# Sheet1.net
KiCad netlist of a schematic drawn in Altium Designer
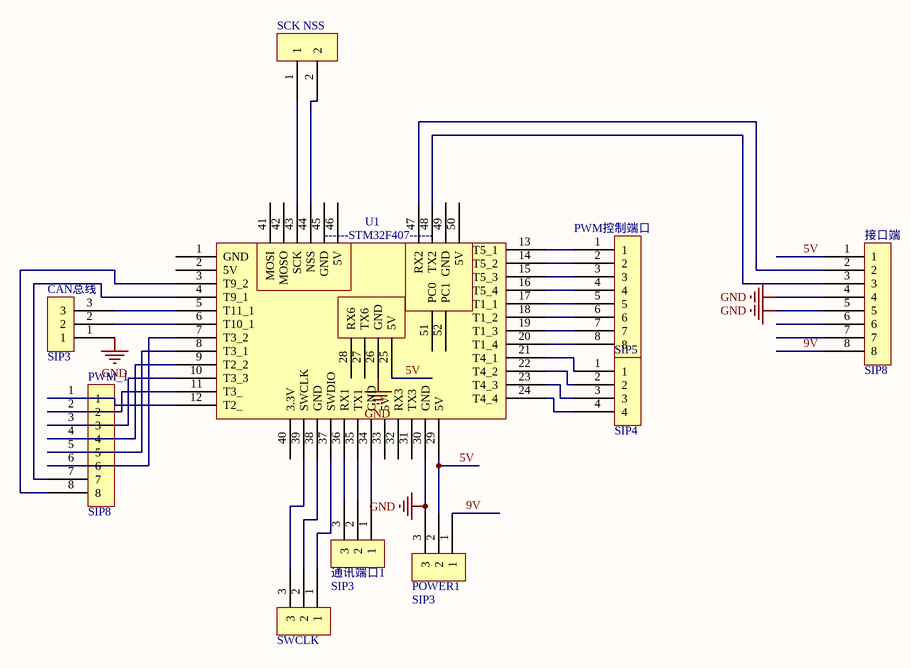
[diagram p0: Sheet1.SchDoc]

(export (version "E")
  (design (tool "Eeschema 10.0.6"))
  (components
    (comp (ref "CAN总线") (value "SIP3") (footprint "SIP3") (libsource (lib "") (part "SIP3_1")))
    (comp (ref "POWER1") (value "SIP3") (footprint "SIP3") (libsource (lib "qudong") (part "SIP3")))
    (comp (ref "PWM_1") (value "SIP8") (footprint "SIP8") (libsource (lib "qudong") (part "SIP8")))
    (comp (ref "PWM控制端口") (value "PWM控制端口") (footprint "SIP8") (libsource (lib "qudong") (part "SIP8")))
    (comp (ref "SCK NSS") (value "SIP2") (footprint "SIP2") (libsource (lib "qudong") (part "SIP2")))
    (comp (ref "SIP5") (value "SIP4") (footprint "SIP4") (libsource (lib "qudong") (part "SIP4")))
    (comp (ref "SWCLK") (value "SIP3") (footprint "SIP3") (libsource (lib "qudong") (part "SIP3")))
    (comp (ref "U1")
      (value "------STM32F407------")
      (footprint "-----STM32F407-----")
      (libsource (lib "qudong") (part "------STM32F407------"))
    )
    (comp (ref "接口端") (value "SIP8") (footprint "SIP8") (libsource (lib "qudong") (part "SIP8")))
    (comp (ref "通讯端口1") (value "SIP3") (footprint "SIP3") (libsource (lib "qudong") (part "SIP3")))
  )
  (nets
    (net (code "1") (name "/5V") (class "Default")
      (node (ref "POWER1") (pin "2") (pinfunction "2_2") (pintype "passive"))
      (node (ref "U1") (pin "25") (pinfunction "5V_25") (pintype "passive"))
      (node (ref "U1") (pin "29") (pinfunction "5V_29") (pintype "passive"))
      (node (ref "接口端") (pin "1") (pinfunction "1_1") (pintype "passive"))
    )
    (net (code "2") (name "/9V") (class "Default")
      (node (ref "POWER1") (pin "1") (pinfunction "1_1") (pintype "passive"))
      (node (ref "接口端") (pin "8") (pinfunction "8_8") (pintype "passive"))
    )
    (net (code "3") (name "GND") (class "Default")
      (node (ref "CAN总线") (pin "1") (pinfunction "1_1") (pintype "passive"))
      (node (ref "POWER1") (pin "3") (pinfunction "3_3") (pintype "passive"))
      (node (ref "U1") (pin "26") (pinfunction "GND_26") (pintype "passive"))
      (node (ref "U1") (pin "30") (pinfunction "GND_30") (pintype "passive"))
      (node (ref "接口端") (pin "4") (pinfunction "4_4") (pintype "passive"))
      (node (ref "接口端") (pin "5") (pinfunction "5_5") (pintype "passive"))
    )
    (net (code "4") (name "Net-(SWCLK-Pad2)") (class "Default")
      (node (ref "SWCLK") (pin "2") (pinfunction "2_2") (pintype "passive"))
      (node (ref "U1") (pin "38") (pinfunction "GND_38") (pintype "passive"))
    )
    (net (code "5") (name "Net-(U1-GND-Pad34)") (class "Default")
      (node (ref "U1") (pin "34") (pinfunction "GND_34") (pintype "passive"))
      (node (ref "通讯端口1") (pin "1") (pinfunction "1_1") (pintype "passive"))
    )
    (net (code "6") (name "Net-(U1-NSS)") (class "Default")
      (node (ref "SCK NSS") (pin "2") (pinfunction "2_2") (pintype "passive"))
      (node (ref "U1") (pin "44") (pinfunction "NSS_44") (pintype "passive"))
    )
    (net (code "7") (name "Net-(U1-RX1)") (class "Default")
      (node (ref "U1") (pin "36") (pinfunction "RX1_36") (pintype "passive"))
      (node (ref "通讯端口1") (pin "3") (pinfunction "3_3") (pintype "passive"))
    )
    (net (code "8") (name "Net-(U1-RX2)") (class "Default")
      (node (ref "U1") (pin "47") (pinfunction "RX2_47") (pintype "passive"))
      (node (ref "接口端") (pin "2") (pinfunction "2_2") (pintype "passive"))
    )
    (net (code "9") (name "Net-(U1-SCK)") (class "Default")
      (node (ref "SCK NSS") (pin "1") (pinfunction "1_1") (pintype "passive"))
      (node (ref "U1") (pin "43") (pinfunction "SCK_43") (pintype "passive"))
    )
    (net (code "10") (name "Net-(U1-SWCLK)") (class "Default")
      (node (ref "SWCLK") (pin "3") (pinfunction "3_3") (pintype "passive"))
      (node (ref "U1") (pin "39") (pinfunction "SWCLK_39") (pintype "passive"))
    )
    (net (code "11") (name "Net-(U1-SWDIO)") (class "Default")
      (node (ref "SWCLK") (pin "1") (pinfunction "1_1") (pintype "passive"))
      (node (ref "U1") (pin "37") (pinfunction "SWDIO_37") (pintype "passive"))
    )
    (net (code "12") (name "Net-(U1-T1_1)") (class "Default")
      (node (ref "PWM控制端口") (pin "5") (pinfunction "5_5") (pintype "passive"))
      (node (ref "U1") (pin "17") (pinfunction "T1_1_17") (pintype "passive"))
    )
    (net (code "13") (name "Net-(U1-T1_2)") (class "Default")
      (node (ref "PWM控制端口") (pin "6") (pinfunction "6_6") (pintype "passive"))
      (node (ref "U1") (pin "18") (pinfunction "T1_2_18") (pintype "passive"))
    )
    (net (code "14") (name "Net-(U1-T1_3)") (class "Default")
      (node (ref "PWM控制端口") (pin "7") (pinfunction "7_7") (pintype "passive"))
      (node (ref "U1") (pin "19") (pinfunction "T1_3_19") (pintype "passive"))
    )
    (net (code "15") (name "Net-(U1-T1_4)") (class "Default")
      (node (ref "PWM控制端口") (pin "8") (pinfunction "8_8") (pintype "passive"))
      (node (ref "U1") (pin "20") (pinfunction "T1_4_20") (pintype "passive"))
    )
    (net (code "16") (name "Net-(U1-T2_)") (class "Default")
      (node (ref "PWM_1") (pin "1") (pinfunction "1_1") (pintype "passive"))
      (node (ref "U1") (pin "12") (pinfunction "T2__12") (pintype "passive"))
    )
    (net (code "17") (name "Net-(U1-T2_2)") (class "Default")
      (node (ref "PWM_1") (pin "4") (pinfunction "4_4") (pintype "passive"))
      (node (ref "U1") (pin "9") (pinfunction "T2_2_9") (pintype "passive"))
    )
    (net (code "18") (name "Net-(U1-T3_)") (class "Default")
      (node (ref "PWM_1") (pin "2") (pinfunction "2_2") (pintype "passive"))
      (node (ref "U1") (pin "11") (pinfunction "T3__11") (pintype "passive"))
    )
    (net (code "19") (name "Net-(U1-T3_1)") (class "Default")
      (node (ref "PWM_1") (pin "5") (pinfunction "5_5") (pintype "passive"))
      (node (ref "U1") (pin "8") (pinfunction "T3_1_8") (pintype "passive"))
    )
    (net (code "20") (name "Net-(U1-T3_2)") (class "Default")
      (node (ref "PWM_1") (pin "6") (pinfunction "6_6") (pintype "passive"))
      (node (ref "U1") (pin "7") (pinfunction "T3_2_7") (pintype "passive"))
    )
    (net (code "21") (name "Net-(U1-T3_3)") (class "Default")
      (node (ref "PWM_1") (pin "3") (pinfunction "3_3") (pintype "passive"))
      (node (ref "U1") (pin "10") (pinfunction "T3_3_10") (pintype "passive"))
    )
    (net (code "22") (name "Net-(U1-T4_1)") (class "Default")
      (node (ref "SIP5") (pin "1") (pinfunction "1_1") (pintype "passive"))
      (node (ref "U1") (pin "21") (pinfunction "T4_1_21") (pintype "passive"))
    )
    (net (code "23") (name "Net-(U1-T4_2)") (class "Default")
      (node (ref "SIP5") (pin "2") (pinfunction "2_2") (pintype "passive"))
      (node (ref "U1") (pin "22") (pinfunction "T4_2_22") (pintype "passive"))
    )
    (net (code "24") (name "Net-(U1-T4_3)") (class "Default")
      (node (ref "SIP5") (pin "3") (pinfunction "3_3") (pintype "passive"))
      (node (ref "U1") (pin "23") (pinfunction "T4_3_23") (pintype "passive"))
    )
    (net (code "25") (name "Net-(U1-T4_4)") (class "Default")
      (node (ref "SIP5") (pin "4") (pinfunction "4_4") (pintype "passive"))
      (node (ref "U1") (pin "24") (pinfunction "T4_4_24") (pintype "passive"))
    )
    (net (code "26") (name "Net-(U1-T5_1)") (class "Default")
      (node (ref "PWM控制端口") (pin "1") (pinfunction "1_1") (pintype "passive"))
      (node (ref "U1") (pin "13") (pinfunction "T5_1_13") (pintype "passive"))
    )
    (net (code "27") (name "Net-(U1-T5_2)") (class "Default")
      (node (ref "PWM控制端口") (pin "2") (pinfunction "2_2") (pintype "passive"))
      (node (ref "U1") (pin "14") (pinfunction "T5_2_14") (pintype "passive"))
    )
    (net (code "28") (name "Net-(U1-T5_3)") (class "Default")
      (node (ref "PWM控制端口") (pin "3") (pinfunction "3_3") (pintype "passive"))
      (node (ref "U1") (pin "15") (pinfunction "T5_3_15") (pintype "passive"))
    )
    (net (code "29") (name "Net-(U1-T5_4)") (class "Default")
      (node (ref "PWM控制端口") (pin "4") (pinfunction "4_4") (pintype "passive"))
      (node (ref "U1") (pin "16") (pinfunction "T5_4_16") (pintype "passive"))
    )
    (net (code "30") (name "Net-(U1-T9_1)") (class "Default")
      (node (ref "PWM_1") (pin "7") (pinfunction "7_7") (pintype "passive"))
      (node (ref "U1") (pin "4") (pinfunction "T9_1_4") (pintype "passive"))
    )
    (net (code "31") (name "Net-(U1-T9_2)") (class "Default")
      (node (ref "PWM_1") (pin "8") (pinfunction "8_8") (pintype "passive"))
      (node (ref "U1") (pin "3") (pinfunction "T9_2_3") (pintype "passive"))
    )
    (net (code "32") (name "Net-(U1-T10_1)") (class "Default")
      (node (ref "CAN总线") (pin "2") (pinfunction "2_2") (pintype "passive"))
      (node (ref "U1") (pin "6") (pinfunction "T10_1_6") (pintype "passive"))
    )
    (net (code "33") (name "Net-(U1-T11_1)") (class "Default")
      (node (ref "CAN总线") (pin "3") (pinfunction "3_3") (pintype "passive"))
      (node (ref "U1") (pin "5") (pinfunction "T11_1_5") (pintype "passive"))
    )
    (net (code "34") (name "Net-(U1-TX1)") (class "Default")
      (node (ref "U1") (pin "35") (pinfunction "TX1_35") (pintype "passive"))
      (node (ref "通讯端口1") (pin "2") (pinfunction "2_2") (pintype "passive"))
    )
    (net (code "35") (name "Net-(U1-TX2)") (class "Default")
      (node (ref "U1") (pin "48") (pinfunction "TX2_48") (pintype "passive"))
      (node (ref "接口端") (pin "3") (pinfunction "3_3") (pintype "passive"))
    )
    (net (code "36") (name "unconnected-(U1-3.3V-Pad40)") (class "Default")
      (node (ref "U1") (pin "40") (pinfunction "3.3V_40") (pintype "passive"))
    )
    (net (code "37") (name "unconnected-(U1-5V-Pad2)") (class "Default")
      (node (ref "U1") (pin "2") (pinfunction "5V_2") (pintype "passive"))
    )
    (net (code "38") (name "unconnected-(U1-5V-Pad33)") (class "Default")
      (node (ref "U1") (pin "33") (pinfunction "5V_33") (pintype "passive"))
    )
    (net (code "39") (name "unconnected-(U1-5V-Pad46)") (class "Default")
      (node (ref "U1") (pin "46") (pinfunction "5V_46") (pintype "passive"))
    )
    (net (code "40") (name "unconnected-(U1-5V-Pad50)") (class "Default")
      (node (ref "U1") (pin "50") (pinfunction "5V_50") (pintype "passive"))
    )
    (net (code "41") (name "unconnected-(U1-GND-Pad1)") (class "Default")
      (node (ref "U1") (pin "1") (pinfunction "GND_1") (pintype "passive"))
    )
    (net (code "42") (name "unconnected-(U1-GND-Pad45)") (class "Default")
      (node (ref "U1") (pin "45") (pinfunction "GND_45") (pintype "passive"))
    )
    (net (code "43") (name "unconnected-(U1-GND-Pad49)") (class "Default")
      (node (ref "U1") (pin "49") (pinfunction "GND_49") (pintype "passive"))
    )
    (net (code "44") (name "unconnected-(U1-MOSI-Pad41)") (class "Default")
      (node (ref "U1") (pin "41") (pinfunction "MOSI_41") (pintype "passive"))
    )
    (net (code "45") (name "unconnected-(U1-MOSO-Pad42)") (class "Default")
      (node (ref "U1") (pin "42") (pinfunction "MOSO_42") (pintype "passive"))
    )
    (net (code "46") (name "unconnected-(U1-PC0-Pad51)") (class "Default")
      (node (ref "U1") (pin "51") (pinfunction "PC0_51") (pintype "passive"))
    )
    (net (code "47") (name "unconnected-(U1-PC1-Pad52)") (class "Default")
      (node (ref "U1") (pin "52") (pinfunction "PC1_52") (pintype "passive"))
    )
    (net (code "48") (name "unconnected-(U1-RX3-Pad32)") (class "Default")
      (node (ref "U1") (pin "32") (pinfunction "RX3_32") (pintype "passive"))
    )
    (net (code "49") (name "unconnected-(U1-RX6-Pad28)") (class "Default")
      (node (ref "U1") (pin "28") (pinfunction "RX6_28") (pintype "passive"))
    )
    (net (code "50") (name "unconnected-(U1-TX3-Pad31)") (class "Default")
      (node (ref "U1") (pin "31") (pinfunction "TX3_31") (pintype "passive"))
    )
    (net (code "51") (name "unconnected-(U1-TX6-Pad27)") (class "Default")
      (node (ref "U1") (pin "27") (pinfunction "TX6_27") (pintype "passive"))
    )
    (net (code "52") (name "unconnected-(接口端-Pad6)") (class "Default")
      (node (ref "接口端") (pin "6") (pinfunction "6_6") (pintype "passive"))
    )
    (net (code "53") (name "unconnected-(接口端-Pad7)") (class "Default")
      (node (ref "接口端") (pin "7") (pinfunction "7_7") (pintype "passive"))
    )
  )
)
